# 09_Misc.net
KiCad netlist of a schematic drawn in Altium Designer
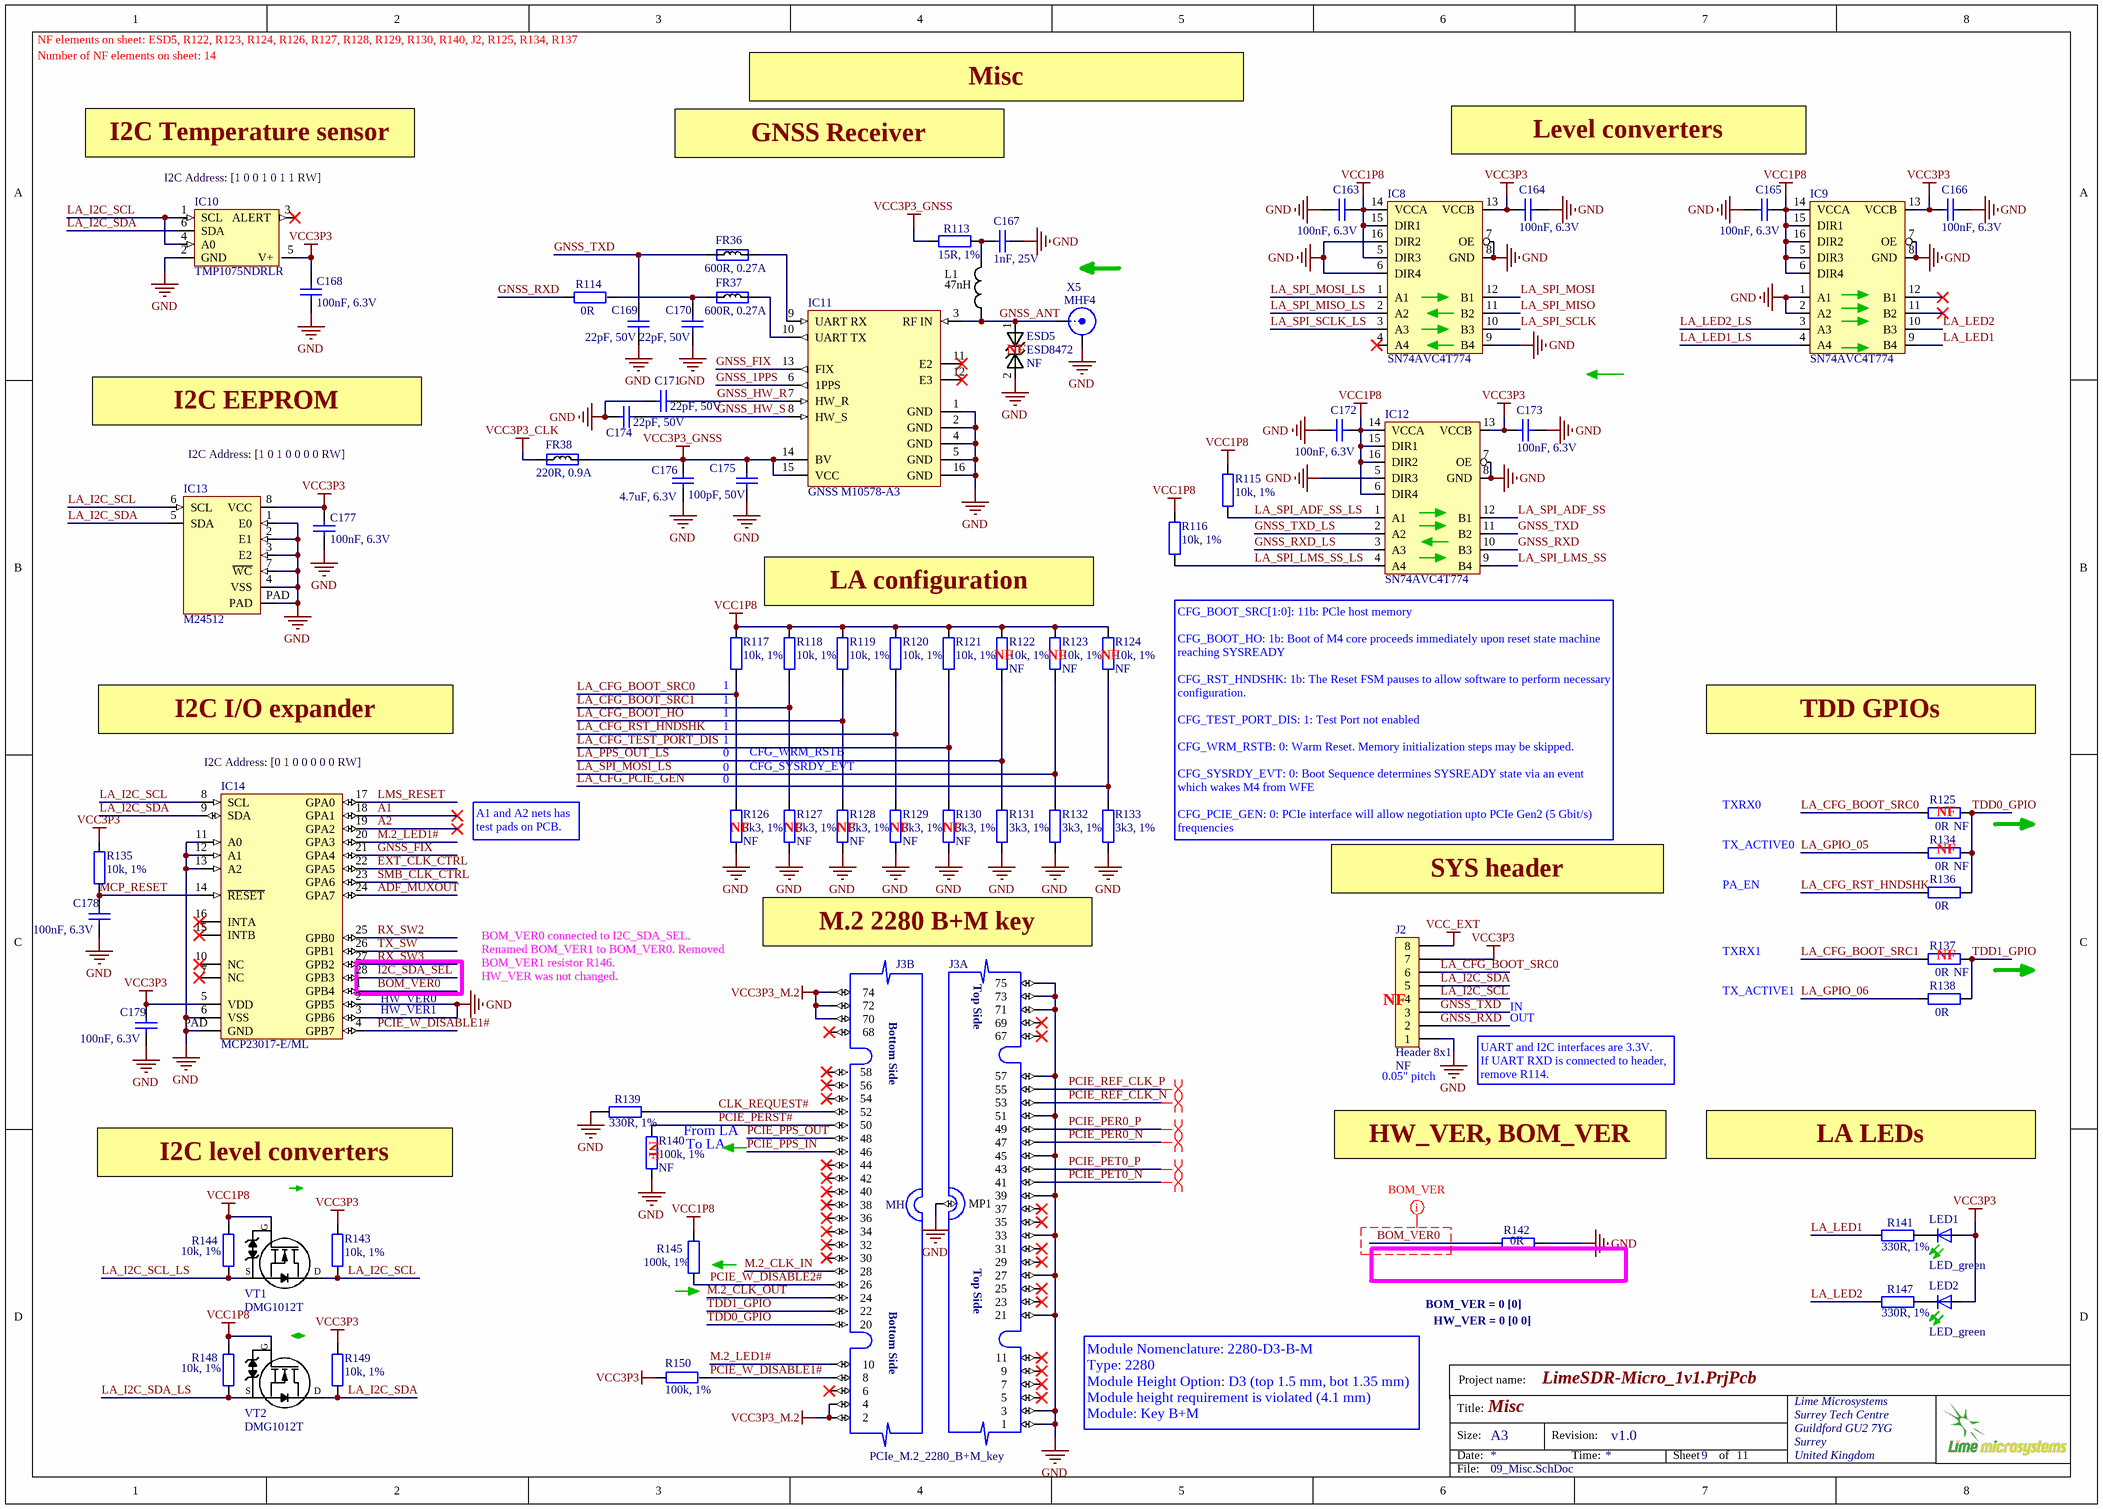
[diagram p0: 09_Misc.SchDoc]

(export (version "E")
  (design (tool "Eeschema 10.0.6"))
  (components
    (comp (ref "C163")
      (value "100nF, 6.3V")
      (footprint "CAP0201")
      (fields (field (name "MANUFACTURER") "Samsung") (field (name "TOLERANCE") "20%"))
      (libsource (lib "LimeMicroAltiumLib_schLib") (part "Cap_0402"))
    )
    (comp (ref "C164")
      (value "100nF, 6.3V")
      (footprint "CAP0201")
      (fields (field (name "MANUFACTURER") "Samsung") (field (name "TOLERANCE") "20%"))
      (libsource (lib "LimeMicroAltiumLib_schLib") (part "Cap_0402"))
    )
    (comp (ref "C165")
      (value "100nF, 6.3V")
      (footprint "CAP0201")
      (fields (field (name "MANUFACTURER") "Samsung") (field (name "TOLERANCE") "20%"))
      (libsource (lib "LimeMicroAltiumLib_schLib") (part "Cap_0402"))
    )
    (comp (ref "C166")
      (value "100nF, 6.3V")
      (footprint "CAP0201")
      (fields (field (name "MANUFACTURER") "Samsung") (field (name "TOLERANCE") "20%"))
      (libsource (lib "LimeMicroAltiumLib_schLib") (part "Cap_0402"))
    )
    (comp (ref "C167")
      (value "1nF, 25V")
      (footprint "CAP0201")
      (fields (field (name "TOLERANCE") "±10%") (field (name "MANUFACTURER") "TDK Corporation"))
      (libsource (lib "LimeMicroAltiumLib_schLib") (part "Cap_0402"))
    )
    (comp (ref "C168")
      (value "100nF, 6.3V")
      (footprint "CAP0201")
      (fields (field (name "MANUFACTURER") "Samsung") (field (name "TOLERANCE") "20%"))
      (libsource (lib "LimeMicroAltiumLib_schLib") (part "Cap_0402"))
    )
    (comp (ref "C169")
      (value "22pF, 50V")
      (footprint "CAP0201")
      (fields
        (field (name "MANUFACTURER") "Murata")
        (field (name "TOLERANCE") "5%")
        (field (name "VOLTAGE") "50V")
      )
      (libsource (lib "LimeMicroAltiumLib_schLib") (part "Cap_0402"))
    )
    (comp (ref "C170")
      (value "22pF, 50V")
      (footprint "CAP0201")
      (fields
        (field (name "MANUFACTURER") "Murata")
        (field (name "TOLERANCE") "5%")
        (field (name "VOLTAGE") "50V")
      )
      (libsource (lib "LimeMicroAltiumLib_schLib") (part "Cap_0402"))
    )
    (comp (ref "C171")
      (value "22pF, 50V")
      (footprint "CAP0201")
      (fields
        (field (name "MANUFACTURER") "Murata")
        (field (name "TOLERANCE") "5%")
        (field (name "VOLTAGE") "50V")
      )
      (libsource (lib "LimeMicroAltiumLib_schLib") (part "Cap_0402"))
    )
    (comp (ref "C172")
      (value "100nF, 6.3V")
      (footprint "CAP0201")
      (fields (field (name "MANUFACTURER") "Samsung") (field (name "TOLERANCE") "20%"))
      (libsource (lib "LimeMicroAltiumLib_schLib") (part "Cap_0402"))
    )
    (comp (ref "C173")
      (value "100nF, 6.3V")
      (footprint "CAP0201")
      (fields (field (name "MANUFACTURER") "Samsung") (field (name "TOLERANCE") "20%"))
      (libsource (lib "LimeMicroAltiumLib_schLib") (part "Cap_0402"))
    )
    (comp (ref "C174")
      (value "22pF, 50V")
      (footprint "CAP0201")
      (fields
        (field (name "MANUFACTURER") "Murata")
        (field (name "TOLERANCE") "5%")
        (field (name "VOLTAGE") "50V")
      )
      (libsource (lib "LimeMicroAltiumLib_schLib") (part "Cap_0402"))
    )
    (comp (ref "C175")
      (value "100pF, 50V")
      (footprint "CAP0201")
      (fields
        (field (name "MANUFACTURER") "TDK")
        (field (name "TOLERANCE") "5%")
        (field (name "VOLTAGE") "50V")
      )
      (libsource (lib "LimeMicroAltiumLib_schLib") (part "Cap_0402"))
    )
    (comp (ref "C176")
      (value "4.7uF, 6.3V")
      (footprint "CAP0402")
      (fields
        (field (name "MANUFACTURER") "Murata Electronics North America")
        (field (name "TOLERANCE") "±20%")
      )
      (libsource (lib "LimeMicroAltiumLib_schLib") (part "Cap_0402"))
    )
    (comp (ref "C177")
      (value "100nF, 6.3V")
      (footprint "CAP0201")
      (fields (field (name "MANUFACTURER") "Samsung") (field (name "TOLERANCE") "20%"))
      (libsource (lib "LimeMicroAltiumLib_schLib") (part "Cap_0402"))
    )
    (comp (ref "C178")
      (value "100nF, 6.3V")
      (footprint "CAP0201")
      (fields (field (name "MANUFACTURER") "Samsung") (field (name "TOLERANCE") "20%"))
      (libsource (lib "LimeMicroAltiumLib_schLib") (part "Cap_0402"))
    )
    (comp (ref "C179")
      (value "100nF, 6.3V")
      (footprint "CAP0201")
      (fields (field (name "MANUFACTURER") "Samsung") (field (name "TOLERANCE") "20%"))
      (libsource (lib "LimeMicroAltiumLib_schLib") (part "Cap_0402"))
    )
    (comp (ref "ESD5")
      (value "ESD8472")
      (footprint "ESD8472_X3DFN2")
      (fields (field (name "MANUFACTURER") "ON Semiconductor") (field (name "ASSEMBLY INFO") "NF"))
      (libsource (lib "LimeMicroAltiumLib_schLib") (part "ESD8472"))
    )
    (comp (ref "FR36")
      (value "600R, 0.27A")
      (footprint "RES0201")
      (fields (field (name "MANUFACTURER") "Taiyo Yuden"))
      (libsource (lib "LimeMicroAltiumLib_schLib") (part "Ferrite"))
    )
    (comp (ref "FR37")
      (value "600R, 0.27A")
      (footprint "RES0201")
      (fields (field (name "MANUFACTURER") "Taiyo Yuden"))
      (libsource (lib "LimeMicroAltiumLib_schLib") (part "Ferrite"))
    )
    (comp (ref "FR38")
      (value "220R, 0.9A")
      (footprint "RES0402")
      (fields (field (name "MANUFACTURER") "TDK Corporation"))
      (libsource (lib "LimeFPGAboard_schLib") (part "Ferrite"))
    )
    (comp (ref "IC8")
      (value "SN74AVC4T774")
      (footprint "SN74AVC4T774_v1")
      (fields (field (name "MANUFACTURER") "Texas Instruments"))
      (libsource (lib "LimeMicroAltiumLib") (part "SN74AVC4T774"))
    )
    (comp (ref "IC9")
      (value "SN74AVC4T774")
      (footprint "SN74AVC4T774_v1")
      (fields (field (name "MANUFACTURER") "Texas Instruments"))
      (libsource (lib "LimeMicroAltiumLib") (part "SN74AVC4T774"))
    )
    (comp (ref "IC10")
      (value "TMP1075NDRLR")
      (footprint "TMP1075NDRLR_temperature_sensor_SOT563")
      (fields (field (name "MANUFACTURER") "Texas Instruments"))
      (libsource (lib "LimeMicroAltiumLib_schLib_r04") (part "TMP1075NDRLR_temperature_sensor"))
    )
    (comp (ref "IC11")
      (value "GNSS M10578-A3")
      (footprint "M10578-A3_v2")
      (fields (field (name "MANUFACTURER") "Antenova"))
      (libsource (lib "LimeMicroAltiumLib_schLib_r04") (part "M10578-A3_GPS_GNSS"))
    )
    (comp (ref "IC12")
      (value "SN74AVC4T774")
      (footprint "SN74AVC4T774_v1")
      (fields (field (name "MANUFACTURER") "Texas Instruments"))
      (libsource (lib "LimeMicroAltiumLib") (part "SN74AVC4T774"))
    )
    (comp (ref "IC13")
      (value "M24512")
      (footprint "M24128-DFMC6TG")
      (fields (field (name "MANUFACTURER") "STMicroelectronics"))
      (libsource (lib "LimeMicroAltiumLib_schLib") (part "M24128-DFMC6TG"))
    )
    (comp (ref "IC14")
      (value "MCP23017-E/ML")
      (footprint "MCP23017-E/ML_QFN28")
      (fields (field (name "MANUFACTURER") "Microchip"))
      (libsource (lib "LimeMicroAltiumLib") (part "MCP23017-E/ML_I2C_expander"))
    )
    (comp (ref "J2")
      (value "Header 8x1")
      (footprint "HEADER_8x1_TH_HALF_PITCH")
      (description "Header, 8-Pin, Single row")
      (fields (field (name "ASSEMBLY INFO") "NF") (field (name "MANUFACTURER") "Harwin"))
      (libsource (lib "LimeMicroAltiumLib") (part "Header 8x1"))
    )
    (comp (ref "J3")
      (value "PCIe_M.2_2280_B+M_key")
      (footprint "PCIe_M.2_2280_B+M_key")
      (libsource (lib "") (part "PCIe_M.2_2280_B+M_key_1"))
    )
    (comp (ref "L1")
      (value "47nH")
      (footprint "RES0402")
      (fields
        (field (name "MANUFACTURER") "COILCRAFT")
        (field (name "MANUFACTURER PART NUMBER") "0402HP-47NXJLU")
      )
      (libsource (lib "LimeMicroAltiumLib_schLib") (part "Inductor_0603"))
    )
    (comp (ref "LED1")
      (value "LED_green")
      (footprint "LED0201")
      (fields (field (name "MANUFACTURER") "Kingbright"))
      (libsource (lib "LimeFPGAboard_schLib") (part "LED_green"))
    )
    (comp (ref "LED2")
      (value "LED_green")
      (footprint "LED0201")
      (fields (field (name "MANUFACTURER") "Kingbright"))
      (libsource (lib "LimeFPGAboard_schLib") (part "LED_green"))
    )
    (comp (ref "R113")
      (value "15R, 1%")
      (footprint "RES0201")
      (fields (field (name "MANUFACTURER") "Yageo") (field (name "TOLERANCE") "1%"))
      (libsource (lib "LimeFPGAboard_schLib") (part "Res_0402"))
    )
    (comp (ref "R114")
      (value "0R")
      (footprint "RES0201")
      (fields (field (name "MANUFACTURER") "Yageo") (field (name "TOLERANCE") "5%"))
      (libsource (lib "LimeFPGAboard_schLib") (part "Res_0402"))
    )
    (comp (ref "R115")
      (value "10k, 1%")
      (footprint "RES0201")
      (fields (field (name "MANUFACTURER") "Yageo") (field (name "TOLERANCE") "1%"))
      (libsource (lib "LimeFPGAboard_schLib") (part "Res_0402"))
    )
    (comp (ref "R116")
      (value "10k, 1%")
      (footprint "RES0201")
      (fields (field (name "MANUFACTURER") "Yageo") (field (name "TOLERANCE") "1%"))
      (libsource (lib "LimeFPGAboard_schLib") (part "Res_0402"))
    )
    (comp (ref "R117")
      (value "10k, 1%")
      (footprint "RES0201")
      (fields (field (name "MANUFACTURER") "Yageo") (field (name "TOLERANCE") "1%"))
      (libsource (lib "LimeFPGAboard_schLib") (part "Res_0402"))
    )
    (comp (ref "R118")
      (value "10k, 1%")
      (footprint "RES0201")
      (fields (field (name "MANUFACTURER") "Yageo") (field (name "TOLERANCE") "1%"))
      (libsource (lib "LimeFPGAboard_schLib") (part "Res_0402"))
    )
    (comp (ref "R119")
      (value "10k, 1%")
      (footprint "RES0201")
      (fields (field (name "MANUFACTURER") "Yageo") (field (name "TOLERANCE") "1%"))
      (libsource (lib "LimeFPGAboard_schLib") (part "Res_0402"))
    )
    (comp (ref "R120")
      (value "10k, 1%")
      (footprint "RES0201")
      (fields (field (name "MANUFACTURER") "Yageo") (field (name "TOLERANCE") "1%"))
      (libsource (lib "LimeFPGAboard_schLib") (part "Res_0402"))
    )
    (comp (ref "R121")
      (value "10k, 1%")
      (footprint "RES0201")
      (fields (field (name "MANUFACTURER") "Yageo") (field (name "TOLERANCE") "1%"))
      (libsource (lib "LimeFPGAboard_schLib") (part "Res_0402"))
    )
    (comp (ref "R122")
      (value "10k, 1%")
      (footprint "RES0201")
      (fields
        (field (name "ASSEMBLY INFO") "NF")
        (field (name "MANUFACTURER") "Yageo")
        (field (name "TOLERANCE") "1%")
      )
      (libsource (lib "LimeFPGAboard_schLib") (part "Res_0402"))
    )
    (comp (ref "R123")
      (value "10k, 1%")
      (footprint "RES0201")
      (fields
        (field (name "ASSEMBLY INFO") "NF")
        (field (name "MANUFACTURER") "Yageo")
        (field (name "TOLERANCE") "1%")
      )
      (libsource (lib "LimeFPGAboard_schLib") (part "Res_0402"))
    )
    (comp (ref "R124")
      (value "10k, 1%")
      (footprint "RES0201")
      (fields
        (field (name "ASSEMBLY INFO") "NF")
        (field (name "MANUFACTURER") "Yageo")
        (field (name "TOLERANCE") "1%")
      )
      (libsource (lib "LimeFPGAboard_schLib") (part "Res_0402"))
    )
    (comp (ref "R125")
      (value "0R")
      (footprint "RES0201")
      (fields
        (field (name "ASSEMBLY INFO") "NF")
        (field (name "MANUFACTURER") "Yageo")
        (field (name "TOLERANCE") "5%")
      )
      (libsource (lib "LimeFPGAboard_schLib") (part "Res_0402"))
    )
    (comp (ref "R126")
      (value "3k3, 1%")
      (footprint "RES0201")
      (fields
        (field (name "ASSEMBLY INFO") "NF")
        (field (name "MANUFACTURER") "Yageo")
        (field (name "TOLERANCE") "1%")
      )
      (libsource (lib "LimeFPGAboard_schLib") (part "Res_0402"))
    )
    (comp (ref "R127")
      (value "3k3, 1%")
      (footprint "RES0201")
      (fields
        (field (name "ASSEMBLY INFO") "NF")
        (field (name "MANUFACTURER") "Yageo")
        (field (name "TOLERANCE") "1%")
      )
      (libsource (lib "LimeFPGAboard_schLib") (part "Res_0402"))
    )
    (comp (ref "R128")
      (value "3k3, 1%")
      (footprint "RES0201")
      (fields
        (field (name "ASSEMBLY INFO") "NF")
        (field (name "MANUFACTURER") "Yageo")
        (field (name "TOLERANCE") "1%")
      )
      (libsource (lib "LimeFPGAboard_schLib") (part "Res_0402"))
    )
    (comp (ref "R129")
      (value "3k3, 1%")
      (footprint "RES0201")
      (fields
        (field (name "ASSEMBLY INFO") "NF")
        (field (name "MANUFACTURER") "Yageo")
        (field (name "TOLERANCE") "1%")
      )
      (libsource (lib "LimeFPGAboard_schLib") (part "Res_0402"))
    )
    (comp (ref "R130")
      (value "3k3, 1%")
      (footprint "RES0201")
      (fields
        (field (name "ASSEMBLY INFO") "NF")
        (field (name "MANUFACTURER") "Yageo")
        (field (name "TOLERANCE") "1%")
      )
      (libsource (lib "LimeFPGAboard_schLib") (part "Res_0402"))
    )
    (comp (ref "R131")
      (value "3k3, 1%")
      (footprint "RES0201")
      (fields (field (name "MANUFACTURER") "Yageo") (field (name "TOLERANCE") "1%"))
      (libsource (lib "LimeFPGAboard_schLib") (part "Res_0402"))
    )
    (comp (ref "R132")
      (value "3k3, 1%")
      (footprint "RES0201")
      (fields (field (name "MANUFACTURER") "Yageo") (field (name "TOLERANCE") "1%"))
      (libsource (lib "LimeFPGAboard_schLib") (part "Res_0402"))
    )
    (comp (ref "R133")
      (value "3k3, 1%")
      (footprint "RES0201")
      (fields (field (name "MANUFACTURER") "Yageo") (field (name "TOLERANCE") "1%"))
      (libsource (lib "LimeFPGAboard_schLib") (part "Res_0402"))
    )
    (comp (ref "R134")
      (value "0R")
      (footprint "RES0201")
      (fields
        (field (name "ASSEMBLY INFO") "NF")
        (field (name "MANUFACTURER") "Yageo")
        (field (name "TOLERANCE") "5%")
      )
      (libsource (lib "LimeFPGAboard_schLib") (part "Res_0402"))
    )
    (comp (ref "R135")
      (value "10k, 1%")
      (footprint "RES0201")
      (fields (field (name "MANUFACTURER") "Yageo") (field (name "TOLERANCE") "1%"))
      (libsource (lib "LimeFPGAboard_schLib") (part "Res_0402"))
    )
    (comp (ref "R136")
      (value "0R")
      (footprint "RES0201")
      (fields (field (name "MANUFACTURER") "Yageo") (field (name "TOLERANCE") "5%"))
      (libsource (lib "LimeFPGAboard_schLib") (part "Res_0402"))
    )
    (comp (ref "R137")
      (value "0R")
      (footprint "RES0201")
      (fields
        (field (name "ASSEMBLY INFO") "NF")
        (field (name "MANUFACTURER") "Yageo")
        (field (name "TOLERANCE") "5%")
      )
      (libsource (lib "LimeFPGAboard_schLib") (part "Res_0402"))
    )
    (comp (ref "R138")
      (value "0R")
      (footprint "RES0201")
      (fields (field (name "MANUFACTURER") "Yageo") (field (name "TOLERANCE") "5%"))
      (libsource (lib "LimeFPGAboard_schLib") (part "Res_0402"))
    )
    (comp (ref "R139")
      (value "330R, 1%")
      (footprint "RES0201")
      (fields (field (name "MANUFACTURER") "Vishay Dale") (field (name "TOLERANCE") "1%"))
      (libsource (lib "LimeFPGAboard_schLib") (part "Res_0402"))
    )
    (comp (ref "R140")
      (value "100k, 1%")
      (footprint "RES0201")
      (fields
        (field (name "ASSEMBLY INFO") "NF")
        (field (name "MANUFACTURER") "Yageo")
        (field (name "TOLERANCE") "1%")
      )
      (libsource (lib "LimeMicroAltiumLib_schLib") (part "Res_0402"))
    )
    (comp (ref "R141")
      (value "330R, 1%")
      (footprint "RES0201")
      (fields (field (name "MANUFACTURER") "Vishay Dale") (field (name "TOLERANCE") "1%"))
      (libsource (lib "LimeFPGAboard_schLib") (part "Res_0402"))
    )
    (comp (ref "R142")
      (value "0R")
      (footprint "RES0201")
      (fields (field (name "MANUFACTURER") "Yageo") (field (name "TOLERANCE") "5%"))
      (libsource (lib "LimeFPGAboard_schLib") (part "Res_0402"))
    )
    (comp (ref "R143")
      (value "10k, 1%")
      (footprint "RES0201")
      (fields (field (name "MANUFACTURER") "Yageo") (field (name "TOLERANCE") "1%"))
      (libsource (lib "LimeFPGAboard_schLib") (part "Res_0402"))
    )
    (comp (ref "R144")
      (value "10k, 1%")
      (footprint "RES0201")
      (fields (field (name "MANUFACTURER") "Yageo") (field (name "TOLERANCE") "1%"))
      (libsource (lib "LimeFPGAboard_schLib") (part "Res_0402"))
    )
    (comp (ref "R145")
      (value "100k, 1%")
      (footprint "RES0201")
      (fields (field (name "MANUFACTURER") "Yageo") (field (name "TOLERANCE") "1%"))
      (libsource (lib "LimeMicroAltiumLib_schLib") (part "Res_0402"))
    )
    (comp (ref "R147")
      (value "330R, 1%")
      (footprint "RES0201")
      (fields (field (name "MANUFACTURER") "Vishay Dale") (field (name "TOLERANCE") "1%"))
      (libsource (lib "LimeFPGAboard_schLib") (part "Res_0402"))
    )
    (comp (ref "R148")
      (value "10k, 1%")
      (footprint "RES0201")
      (fields (field (name "MANUFACTURER") "Yageo") (field (name "TOLERANCE") "1%"))
      (libsource (lib "LimeFPGAboard_schLib") (part "Res_0402"))
    )
    (comp (ref "R149")
      (value "10k, 1%")
      (footprint "RES0201")
      (fields (field (name "MANUFACTURER") "Yageo") (field (name "TOLERANCE") "1%"))
      (libsource (lib "LimeFPGAboard_schLib") (part "Res_0402"))
    )
    (comp (ref "R150")
      (value "100k, 1%")
      (footprint "RES0201")
      (fields (field (name "MANUFACTURER") "Yageo") (field (name "TOLERANCE") "1%"))
      (libsource (lib "LimeMicroAltiumLib_schLib") (part "Res_0402"))
    )
    (comp (ref "VT1")
      (value "DMG1012T")
      (footprint "SOT523")
      (fields (field (name "MANUFACTURER") "Diodes Incorporated"))
      (libsource (lib "LimeMicroAltiumLib_schLib_r01") (part "DMG1012T"))
    )
    (comp (ref "VT2")
      (value "DMG1012T")
      (footprint "SOT523")
      (fields (field (name "MANUFACTURER") "Diodes Incorporated"))
      (libsource (lib "LimeMicroAltiumLib_schLib_r01") (part "DMG1012T"))
    )
    (comp (ref "X5")
      (value "MHF4")
      (footprint "IPEX_MHF4_conn")
      (description "IPEX MHF4 Connector Jack, Male Pin 50 Ohms Surface Mount Solder")
      (fields (field (name "MANUFACTURER") "TE Connectivity / Linx Technologies"))
      (libsource (lib "LimeMicroAltiumLib_schLib") (part "RF_IF_connector"))
    )
  )
  (nets
    (net (code "1") (name "/A1") (class "Default")
      (node (ref "IC14") (pin "18") (pinfunction "GPA1_18") (pintype "bidirectional+no_connect"))
    )
    (net (code "2") (name "/A2") (class "Default")
      (node (ref "IC14") (pin "19") (pinfunction "GPA2_19") (pintype "bidirectional+no_connect"))
    )
    (net (code "3") (name "/ADF_MUXOUT") (class "Default")
      (node (ref "IC14") (pin "24") (pinfunction "GPA7_24") (pintype "bidirectional"))
    )
    (net (code "4") (name "/BOM_VER0") (class "Default")
      (node (ref "IC14") (pin "1") (pinfunction "GPB4_1") (pintype "bidirectional"))
      (node (ref "R142") (pin "1") (pinfunction "1_1") (pintype "passive"))
    )
    (net (code "5") (name "/CLK_REQUEST#") (class "Default")
      (node (ref "J3") (pin "P52") (pinfunction "52_P52") (pintype "bidirectional"))
      (node (ref "R139") (pin "1") (pinfunction "1_1") (pintype "passive"))
    )
    (net (code "6") (name "/EXT_CLK_CTRL") (class "Default")
      (node (ref "IC14") (pin "22") (pinfunction "GPA5_22") (pintype "bidirectional"))
    )
    (net (code "7") (name "/GNSS_1PPS") (class "Default")
      (node (ref "IC11") (pin "6") (pinfunction "1PPS_6") (pintype "output"))
    )
    (net (code "8") (name "/GNSS_ANT") (class "Default")
      (node (ref "ESD5") (pin "1") (pinfunction "1_1") (pintype "passive"))
      (node (ref "IC11") (pin "3") (pinfunction "RF_IN_3") (pintype "input"))
      (node (ref "L1") (pin "1") (pinfunction "1_1") (pintype "passive"))
      (node (ref "X5") (pin "1") (pinfunction "X_1") (pintype "passive"))
    )
    (net (code "9") (name "/GNSS_FIX") (class "Default")
      (node (ref "IC11") (pin "13") (pinfunction "FIX_13") (pintype "output"))
      (node (ref "IC14") (pin "21") (pinfunction "GPA4_21") (pintype "bidirectional"))
    )
    (net (code "10") (name "/GNSS_HW_R") (class "Default")
      (node (ref "C171") (pin "1") (pinfunction "1_1") (pintype "passive"))
      (node (ref "IC11") (pin "7") (pinfunction "HW_R_7") (pintype "input"))
    )
    (net (code "11") (name "/GNSS_HW_S") (class "Default")
      (node (ref "C174") (pin "1") (pinfunction "1_1") (pintype "passive"))
      (node (ref "IC11") (pin "8") (pinfunction "HW_S_8") (pintype "input"))
    )
    (net (code "12") (name "/GNSS_RXD") (class "Default")
      (node (ref "IC12") (pin "10") (pinfunction "B3_10") (pintype "passive"))
      (node (ref "J2") (pin "2") (pinfunction "2_2") (pintype "passive"))
      (node (ref "R114") (pin "1") (pinfunction "1_1") (pintype "passive"))
    )
    (net (code "13") (name "/GNSS_RXD_LS") (class "Default")
      (node (ref "IC12") (pin "3") (pinfunction "A3_3") (pintype "passive"))
    )
    (net (code "14") (name "/GNSS_TXD") (class "Default")
      (node (ref "C169") (pin "1") (pinfunction "1_1") (pintype "passive"))
      (node (ref "FR36") (pin "1") (pinfunction "1_1") (pintype "passive"))
      (node (ref "IC12") (pin "11") (pinfunction "B2_11") (pintype "passive"))
      (node (ref "J2") (pin "3") (pinfunction "3_3") (pintype "passive"))
    )
    (net (code "15") (name "/GNSS_TXD_LS") (class "Default")
      (node (ref "IC12") (pin "2") (pinfunction "A2_2") (pintype "passive"))
    )
    (net (code "16") (name "/I2C_SDA_SEL") (class "Default")
      (node (ref "IC14") (pin "28") (pinfunction "GPB3_28") (pintype "bidirectional"))
    )
    (net (code "17") (name "/LA_CFG_BOOT_HO") (class "Default")
      (node (ref "R119") (pin "2") (pinfunction "2_2") (pintype "passive"))
      (node (ref "R128") (pin "1") (pinfunction "1_1") (pintype "passive"))
    )
    (net (code "18") (name "/LA_CFG_BOOT_SRC0") (class "Default")
      (node (ref "J2") (pin "6") (pinfunction "6_6") (pintype "passive"))
      (node (ref "R117") (pin "2") (pinfunction "2_2") (pintype "passive"))
      (node (ref "R125") (pin "1") (pinfunction "1_1") (pintype "passive"))
      (node (ref "R126") (pin "1") (pinfunction "1_1") (pintype "passive"))
    )
    (net (code "19") (name "/LA_CFG_BOOT_SRC1") (class "Default")
      (node (ref "R118") (pin "2") (pinfunction "2_2") (pintype "passive"))
      (node (ref "R127") (pin "1") (pinfunction "1_1") (pintype "passive"))
      (node (ref "R137") (pin "1") (pinfunction "1_1") (pintype "passive"))
    )
    (net (code "20") (name "/LA_CFG_PCIE_GEN") (class "Default")
      (node (ref "R124") (pin "2") (pinfunction "2_2") (pintype "passive"))
      (node (ref "R133") (pin "1") (pinfunction "1_1") (pintype "passive"))
    )
    (net (code "21") (name "/LA_CFG_RST_HNDSHK") (class "Default")
      (node (ref "R120") (pin "2") (pinfunction "2_2") (pintype "passive"))
      (node (ref "R129") (pin "1") (pinfunction "1_1") (pintype "passive"))
      (node (ref "R136") (pin "1") (pinfunction "1_1") (pintype "passive"))
    )
    (net (code "22") (name "/LA_CFG_TEST_PORT_DIS") (class "Default")
      (node (ref "R121") (pin "2") (pinfunction "2_2") (pintype "passive"))
      (node (ref "R130") (pin "1") (pinfunction "1_1") (pintype "passive"))
    )
    (net (code "23") (name "/LA_GPIO_05") (class "Default")
      (node (ref "R134") (pin "1") (pinfunction "1_1") (pintype "passive"))
    )
    (net (code "24") (name "/LA_GPIO_06") (class "Default")
      (node (ref "R138") (pin "1") (pinfunction "1_1") (pintype "passive"))
    )
    (net (code "25") (name "/LA_I2C_SCL") (class "Default")
      (node (ref "IC10") (pin "1") (pinfunction "SCL_1") (pintype "input"))
      (node (ref "IC10") (pin "4") (pinfunction "A0_4") (pintype "input"))
      (node (ref "IC13") (pin "6") (pinfunction "SCL_6") (pintype "input"))
      (node (ref "IC14") (pin "8") (pinfunction "SCL_8") (pintype "input"))
      (node (ref "J2") (pin "4") (pinfunction "4_4") (pintype "passive"))
      (node (ref "R143") (pin "2") (pinfunction "2_2") (pintype "passive"))
      (node (ref "VT1") (pin "D") (pinfunction "D_D") (pintype "passive"))
    )
    (net (code "26") (name "/LA_I2C_SCL_LS") (class "Default")
      (node (ref "R144") (pin "2") (pinfunction "2_2") (pintype "passive"))
      (node (ref "VT1") (pin "S") (pinfunction "S_S") (pintype "passive"))
    )
    (net (code "27") (name "/LA_I2C_SDA") (class "Default")
      (node (ref "IC10") (pin "6") (pinfunction "SDA_6") (pintype "bidirectional"))
      (node (ref "IC13") (pin "5") (pinfunction "SDA_5") (pintype "bidirectional"))
      (node (ref "IC14") (pin "9") (pinfunction "SDA_9") (pintype "bidirectional"))
      (node (ref "J2") (pin "5") (pinfunction "5_5") (pintype "passive"))
      (node (ref "R149") (pin "2") (pinfunction "2_2") (pintype "passive"))
      (node (ref "VT2") (pin "D") (pinfunction "D_D") (pintype "passive"))
    )
    (net (code "28") (name "/LA_I2C_SDA_LS") (class "Default")
      (node (ref "R148") (pin "2") (pinfunction "2_2") (pintype "passive"))
      (node (ref "VT2") (pin "S") (pinfunction "S_S") (pintype "passive"))
    )
    (net (code "29") (name "/LA_LED1") (class "Default")
      (node (ref "IC9") (pin "9") (pinfunction "B4_9") (pintype "passive"))
      (node (ref "R141") (pin "2") (pinfunction "2_2") (pintype "passive"))
    )
    (net (code "30") (name "/LA_LED1_LS") (class "Default")
      (node (ref "IC9") (pin "4") (pinfunction "A4_4") (pintype "passive"))
    )
    (net (code "31") (name "/LA_LED2") (class "Default")
      (node (ref "IC9") (pin "10") (pinfunction "B3_10") (pintype "passive"))
      (node (ref "R147") (pin "2") (pinfunction "2_2") (pintype "passive"))
    )
    (net (code "32") (name "/LA_LED2_LS") (class "Default")
      (node (ref "IC9") (pin "3") (pinfunction "A3_3") (pintype "passive"))
    )
    (net (code "33") (name "/LA_PPS_OUT_LS") (class "Default")
      (node (ref "R122") (pin "2") (pinfunction "2_2") (pintype "passive"))
      (node (ref "R131") (pin "1") (pinfunction "1_1") (pintype "passive"))
    )
    (net (code "34") (name "/LA_SPI_ADF_SS") (class "Default")
      (node (ref "IC12") (pin "12") (pinfunction "B1_12") (pintype "passive"))
    )
    (net (code "35") (name "/LA_SPI_ADF_SS_LS") (class "Default")
      (node (ref "IC12") (pin "1") (pinfunction "A1_1") (pintype "passive"))
      (node (ref "R115") (pin "2") (pinfunction "2_2") (pintype "passive"))
    )
    (net (code "36") (name "/LA_SPI_LMS_SS") (class "Default")
      (node (ref "IC12") (pin "9") (pinfunction "B4_9") (pintype "passive"))
    )
    (net (code "37") (name "/LA_SPI_LMS_SS_LS") (class "Default")
      (node (ref "IC12") (pin "4") (pinfunction "A4_4") (pintype "passive"))
      (node (ref "R116") (pin "2") (pinfunction "2_2") (pintype "passive"))
    )
    (net (code "38") (name "/LA_SPI_MISO") (class "Default")
      (node (ref "IC8") (pin "11") (pinfunction "B2_11") (pintype "passive"))
    )
    (net (code "39") (name "/LA_SPI_MISO_LS") (class "Default")
      (node (ref "IC8") (pin "2") (pinfunction "A2_2") (pintype "passive"))
    )
    (net (code "40") (name "/LA_SPI_MOSI") (class "Default")
      (node (ref "IC8") (pin "12") (pinfunction "B1_12") (pintype "passive"))
    )
    (net (code "41") (name "/LA_SPI_MOSI_LS") (class "Default")
      (node (ref "IC8") (pin "1") (pinfunction "A1_1") (pintype "passive"))
      (node (ref "R123") (pin "2") (pinfunction "2_2") (pintype "passive"))
      (node (ref "R132") (pin "1") (pinfunction "1_1") (pintype "passive"))
    )
    (net (code "42") (name "/LA_SPI_SCLK") (class "Default")
      (node (ref "IC8") (pin "10") (pinfunction "B3_10") (pintype "passive"))
    )
    (net (code "43") (name "/LA_SPI_SCLK_LS") (class "Default")
      (node (ref "IC8") (pin "3") (pinfunction "A3_3") (pintype "passive"))
    )
    (net (code "44") (name "/LMS_RESET") (class "Default")
      (node (ref "IC14") (pin "17") (pinfunction "GPA0_17") (pintype "bidirectional"))
    )
    (net (code "45") (name "/M.2_CLK_IN") (class "Default")
      (node (ref "J3") (pin "P28") (pinfunction "28_P28") (pintype "bidirectional"))
    )
    (net (code "46") (name "/M.2_CLK_OUT") (class "Default")
      (node (ref "J3") (pin "P24") (pinfunction "24_P24") (pintype "bidirectional"))
    )
    (net (code "47") (name "/M.2_LED1#") (class "Default")
      (node (ref "IC14") (pin "20") (pinfunction "GPA3_20") (pintype "bidirectional"))
      (node (ref "J3") (pin "P10") (pinfunction "10_P10") (pintype "bidirectional"))
    )
    (net (code "48") (name "/MCP_RESET") (class "Default")
      (node (ref "C178") (pin "1") (pinfunction "1_1") (pintype "passive"))
      (node (ref "IC14") (pin "14") (pinfunction "~{RESET}_14") (pintype "input"))
      (node (ref "R135") (pin "2") (pinfunction "2_2") (pintype "passive"))
    )
    (net (code "49") (name "/PCIE_PER0_N") (class "Default")
      (node (ref "J3") (pin "P47") (pinfunction "47_P47") (pintype "bidirectional"))
    )
    (net (code "50") (name "/PCIE_PER0_P") (class "Default")
      (node (ref "J3") (pin "P49") (pinfunction "49_P49") (pintype "bidirectional"))
    )
    (net (code "51") (name "/PCIE_PERST#") (class "Default")
      (node (ref "J3") (pin "P50") (pinfunction "50_P50") (pintype "bidirectional"))
      (node (ref "R140") (pin "2") (pinfunction "2_2") (pintype "passive"))
    )
    (net (code "52") (name "/PCIE_PET0_N") (class "Default")
      (node (ref "J3") (pin "P41") (pinfunction "41_P41") (pintype "bidirectional"))
    )
    (net (code "53") (name "/PCIE_PET0_P") (class "Default")
      (node (ref "J3") (pin "P43") (pinfunction "43_P43") (pintype "bidirectional"))
    )
    (net (code "54") (name "/PCIE_PPS_IN") (class "Default")
      (node (ref "J3") (pin "P46") (pinfunction "46_P46") (pintype "bidirectional"))
    )
    (net (code "55") (name "/PCIE_PPS_OUT") (class "Default")
      (node (ref "J3") (pin "P48") (pinfunction "48_P48") (pintype "bidirectional"))
    )
    (net (code "56") (name "/PCIE_REF_CLK_N") (class "Default")
      (node (ref "J3") (pin "P53") (pinfunction "53_P53") (pintype "bidirectional"))
    )
    (net (code "57") (name "/PCIE_REF_CLK_P") (class "Default")
      (node (ref "J3") (pin "P55") (pinfunction "55_P55") (pintype "bidirectional"))
    )
    (net (code "58") (name "/PCIE_W_DISABLE1#") (class "Default")
      (node (ref "IC14") (pin "4") (pinfunction "GPB7_4") (pintype "bidirectional"))
      (node (ref "J3") (pin "P8") (pinfunction "8_P8") (pintype "bidirectional"))
      (node (ref "R150") (pin "2") (pinfunction "2_2") (pintype "passive"))
    )
    (net (code "59") (name "/PCIE_W_DISABLE2#") (class "Default")
      (node (ref "J3") (pin "P26") (pinfunction "26_P26") (pintype "bidirectional"))
      (node (ref "R145") (pin "2") (pinfunction "2_2") (pintype "passive"))
    )
    (net (code "60") (name "/RX_SW2") (class "Default")
      (node (ref "IC14") (pin "25") (pinfunction "GPB0_25") (pintype "bidirectional"))
    )
    (net (code "61") (name "/RX_SW3") (class "Default")
      (node (ref "IC14") (pin "27") (pinfunction "GPB2_27") (pintype "bidirectional"))
    )
    (net (code "62") (name "/SMB_CLK_CTRL") (class "Default")
      (node (ref "IC14") (pin "23") (pinfunction "GPA6_23") (pintype "bidirectional"))
    )
    (net (code "63") (name "/TDD0_GPIO") (class "Default")
      (node (ref "J3") (pin "P20") (pinfunction "20_P20") (pintype "bidirectional"))
      (node (ref "R125") (pin "2") (pinfunction "2_2") (pintype "passive"))
      (node (ref "R134") (pin "2") (pinfunction "2_2") (pintype "passive"))
      (node (ref "R136") (pin "2") (pinfunction "2_2") (pintype "passive"))
    )
    (net (code "64") (name "/TDD1_GPIO") (class "Default")
      (node (ref "J3") (pin "P22") (pinfunction "22_P22") (pintype "bidirectional"))
      (node (ref "R137") (pin "2") (pinfunction "2_2") (pintype "passive"))
      (node (ref "R138") (pin "2") (pinfunction "2_2") (pintype "passive"))
    )
    (net (code "65") (name "/TX_SW") (class "Default")
      (node (ref "IC14") (pin "26") (pinfunction "GPB1_26") (pintype "bidirectional"))
    )
    (net (code "66") (name "GND") (class "Default")
      (node (ref "C163") (pin "1") (pinfunction "1_1") (pintype "passive"))
      (node (ref "C164") (pin "2") (pinfunction "2_2") (pintype "passive"))
      (node (ref "C165") (pin "1") (pinfunction "1_1") (pintype "passive"))
      (node (ref "C166") (pin "2") (pinfunction "2_2") (pintype "passive"))
      (node (ref "C167") (pin "2") (pinfunction "2_2") (pintype "passive"))
      (node (ref "C168") (pin "2") (pinfunction "2_2") (pintype "passive"))
      (node (ref "C169") (pin "2") (pinfunction "2_2") (pintype "passive"))
      (node (ref "C170") (pin "2") (pinfunction "2_2") (pintype "passive"))
      (node (ref "C171") (pin "2") (pinfunction "2_2") (pintype "passive"))
      (node (ref "C172") (pin "1") (pinfunction "1_1") (pintype "passive"))
      (node (ref "C173") (pin "2") (pinfunction "2_2") (pintype "passive"))
      (node (ref "C174") (pin "2") (pinfunction "2_2") (pintype "passive"))
      (node (ref "C175") (pin "1") (pinfunction "1_1") (pintype "passive"))
      (node (ref "C176") (pin "1") (pinfunction "1_1") (pintype "passive"))
      (node (ref "C177") (pin "2") (pinfunction "2_2") (pintype "passive"))
      (node (ref "C178") (pin "2") (pinfunction "2_2") (pintype "passive"))
      (node (ref "C179") (pin "2") (pinfunction "2_2") (pintype "passive"))
      (node (ref "ESD5") (pin "2") (pinfunction "2_2") (pintype "passive"))
      (node (ref "IC10") (pin "2") (pinfunction "GND_2") (pintype "passive"))
      (node (ref "IC11") (pin "1") (pinfunction "GND_1") (pintype "passive"))
      (node (ref "IC11") (pin "16") (pinfunction "GND_16") (pintype "passive"))
      (node (ref "IC11") (pin "2") (pinfunction "GND_2") (pintype "passive"))
      (node (ref "IC11") (pin "4") (pinfunction "GND_4") (pintype "passive"))
      (node (ref "IC11") (pin "5") (pinfunction "GND_5") (pintype "passive"))
      (node (ref "IC12") (pin "5") (pinfunction "DIR3_5") (pintype "passive"))
      (node (ref "IC12") (pin "7") (pinfunction "OE_7") (pintype "passive"))
      (node (ref "IC12") (pin "8") (pinfunction "GND_8") (pintype "passive"))
      (node (ref "IC13") (pin "1") (pinfunction "E0_1") (pintype "input"))
      (node (ref "IC13") (pin "2") (pinfunction "E1_2") (pintype "input"))
      (node (ref "IC13") (pin "3") (pinfunction "E2_3") (pintype "input"))
      (node (ref "IC13") (pin "4") (pinfunction "VSS_4") (pintype "power_in"))
      (node (ref "IC13") (pin "7") (pinfunction "~{WC}_7") (pintype "input"))
      (node (ref "IC13") (pin "PAD") (pinfunction "PAD_PAD") (pintype "power_in"))
      (node (ref "IC14") (pin "11") (pinfunction "A0_11") (pintype "input"))
      (node (ref "IC14") (pin "12") (pinfunction "A1_12") (pintype "input"))
      (node (ref "IC14") (pin "13") (pinfunction "A2_13") (pintype "input"))
      (node (ref "IC14") (pin "2") (pinfunction "GPB5_2") (pintype "bidirectional"))
      (node (ref "IC14") (pin "3") (pinfunction "GPB6_3") (pintype "bidirectional"))
      (node (ref "IC14") (pin "6") (pinfunction "VSS_6") (pintype "power_in"))
      (node (ref "IC14") (pin "PAD") (pinfunction "GND_PAD") (pintype "passive"))
      (node (ref "IC8") (pin "16") (pinfunction "DIR2_16") (pintype "passive"))
      (node (ref "IC8") (pin "6") (pinfunction "DIR4_6") (pintype "passive"))
      (node (ref "IC8") (pin "7") (pinfunction "OE_7") (pintype "passive"))
      (node (ref "IC8") (pin "8") (pinfunction "GND_8") (pintype "passive"))
      (node (ref "IC8") (pin "9") (pinfunction "B4_9") (pintype "passive"))
      (node (ref "IC9") (pin "1") (pinfunction "A1_1") (pintype "passive"))
      (node (ref "IC9") (pin "2") (pinfunction "A2_2") (pintype "passive"))
      (node (ref "IC9") (pin "7") (pinfunction "OE_7") (pintype "passive"))
      (node (ref "IC9") (pin "8") (pinfunction "GND_8") (pintype "passive"))
      (node (ref "J2") (pin "1") (pinfunction "1_1") (pintype "passive"))
      (node (ref "J3") (pin "MOUNTING-HOLE") (pinfunction "MP1_MOUNTING-HOLE") (pintype "bidirectional"))
      (node (ref "J3") (pin "P1") (pinfunction "1_P1") (pintype "bidirectional"))
      (node (ref "J3") (pin "P21") (pinfunction "21_P21") (pintype "bidirectional"))
      (node (ref "J3") (pin "P27") (pinfunction "27_P27") (pintype "bidirectional"))
      (node (ref "J3") (pin "P3") (pinfunction "3_P3") (pintype "bidirectional"))
      (node (ref "J3") (pin "P33") (pinfunction "33_P33") (pintype "bidirectional"))
      (node (ref "J3") (pin "P39") (pinfunction "39_P39") (pintype "bidirectional"))
      (node (ref "J3") (pin "P45") (pinfunction "45_P45") (pintype "bidirectional"))
      (node (ref "J3") (pin "P51") (pinfunction "51_P51") (pintype "bidirectional"))
      (node (ref "J3") (pin "P57") (pinfunction "57_P57") (pintype "bidirectional"))
      (node (ref "J3") (pin "P71") (pinfunction "71_P71") (pintype "bidirectional"))
      (node (ref "J3") (pin "P73") (pinfunction "73_P73") (pintype "bidirectional"))
      (node (ref "J3") (pin "P75") (pinfunction "75_P75") (pintype "bidirectional"))
      (node (ref "R126") (pin "2") (pinfunction "2_2") (pintype "passive"))
      (node (ref "R127") (pin "2") (pinfunction "2_2") (pintype "passive"))
      (node (ref "R128") (pin "2") (pinfunction "2_2") (pintype "passive"))
      (node (ref "R129") (pin "2") (pinfunction "2_2") (pintype "passive"))
      (node (ref "R130") (pin "2") (pinfunction "2_2") (pintype "passive"))
      (node (ref "R131") (pin "2") (pinfunction "2_2") (pintype "passive"))
      (node (ref "R132") (pin "2") (pinfunction "2_2") (pintype "passive"))
      (node (ref "R133") (pin "2") (pinfunction "2_2") (pintype "passive"))
      (node (ref "R139") (pin "2") (pinfunction "2_2") (pintype "passive"))
      (node (ref "R140") (pin "1") (pinfunction "1_1") (pintype "passive"))
      (node (ref "R142") (pin "2") (pinfunction "2_2") (pintype "passive"))
      (node (ref "X5") (pin "2") (pinfunction "Y_2") (pintype "passive"))
    )
    (net (code "67") (name "Net-(C167-Pad1)") (class "Default")
      (node (ref "C167") (pin "1") (pinfunction "1_1") (pintype "passive"))
      (node (ref "L1") (pin "2") (pinfunction "2_2") (pintype "passive"))
      (node (ref "R113") (pin "1") (pinfunction "1_1") (pintype "passive"))
    )
    (net (code "68") (name "Net-(C170-Pad1)") (class "Default")
      (node (ref "C170") (pin "1") (pinfunction "1_1") (pintype "passive"))
      (node (ref "FR37") (pin "1") (pinfunction "1_1") (pintype "passive"))
      (node (ref "R114") (pin "2") (pinfunction "2_2") (pintype "passive"))
    )
    (net (code "69") (name "Net-(IC11-UART_RX)") (class "Default")
      (node (ref "FR36") (pin "2") (pinfunction "2_2") (pintype "passive"))
      (node (ref "IC11") (pin "9") (pinfunction "UART_RX_9") (pintype "input"))
    )
    (net (code "70") (name "Net-(IC11-UART_TX)") (class "Default")
      (node (ref "FR37") (pin "2") (pinfunction "2_2") (pintype "passive"))
      (node (ref "IC11") (pin "10") (pinfunction "UART_TX_10") (pintype "output"))
    )
    (net (code "71") (name "Net-(LED1-C)") (class "Default")
      (node (ref "LED1") (pin "K") (pinfunction "C_K") (pintype "power_in"))
      (node (ref "R141") (pin "1") (pinfunction "1_1") (pintype "passive"))
    )
    (net (code "72") (name "Net-(LED2-C)") (class "Default")
      (node (ref "LED2") (pin "K") (pinfunction "C_K") (pintype "power_in"))
      (node (ref "R147") (pin "1") (pinfunction "1_1") (pintype "passive"))
    )
    (net (code "73") (name "VCC1P8") (class "Default")
      (node (ref "C163") (pin "2") (pinfunction "2_2") (pintype "passive"))
      (node (ref "C165") (pin "2") (pinfunction "2_2") (pintype "passive"))
      (node (ref "C172") (pin "2") (pinfunction "2_2") (pintype "passive"))
      (node (ref "IC12") (pin "14") (pinfunction "VCCA_14") (pintype "passive"))
      (node (ref "IC12") (pin "15") (pinfunction "DIR1_15") (pintype "passive"))
      (node (ref "IC12") (pin "16") (pinfunction "DIR2_16") (pintype "passive"))
      (node (ref "IC12") (pin "6") (pinfunction "DIR4_6") (pintype "passive"))
      (node (ref "IC8") (pin "14") (pinfunction "VCCA_14") (pintype "passive"))
      (node (ref "IC8") (pin "15") (pinfunction "DIR1_15") (pintype "passive"))
      (node (ref "IC8") (pin "5") (pinfunction "DIR3_5") (pintype "passive"))
      (node (ref "IC9") (pin "14") (pinfunction "VCCA_14") (pintype "passive"))
      (node (ref "IC9") (pin "15") (pinfunction "DIR1_15") (pintype "passive"))
      (node (ref "IC9") (pin "16") (pinfunction "DIR2_16") (pintype "passive"))
      (node (ref "IC9") (pin "5") (pinfunction "DIR3_5") (pintype "passive"))
      (node (ref "IC9") (pin "6") (pinfunction "DIR4_6") (pintype "passive"))
      (node (ref "R115") (pin "1") (pinfunction "1_1") (pintype "passive"))
      (node (ref "R116") (pin "1") (pinfunction "1_1") (pintype "passive"))
      (node (ref "R117") (pin "1") (pinfunction "1_1") (pintype "passive"))
      (node (ref "R118") (pin "1") (pinfunction "1_1") (pintype "passive"))
      (node (ref "R119") (pin "1") (pinfunction "1_1") (pintype "passive"))
      (node (ref "R120") (pin "1") (pinfunction "1_1") (pintype "passive"))
      (node (ref "R121") (pin "1") (pinfunction "1_1") (pintype "passive"))
      (node (ref "R122") (pin "1") (pinfunction "1_1") (pintype "passive"))
      (node (ref "R123") (pin "1") (pinfunction "1_1") (pintype "passive"))
      (node (ref "R124") (pin "1") (pinfunction "1_1") (pintype "passive"))
      (node (ref "R144") (pin "1") (pinfunction "1_1") (pintype "passive"))
      (node (ref "R145") (pin "1") (pinfunction "1_1") (pintype "passive"))
      (node (ref "R148") (pin "1") (pinfunction "1_1") (pintype "passive"))
      (node (ref "VT1") (pin "G") (pinfunction "G_G") (pintype "passive"))
      (node (ref "VT2") (pin "G") (pinfunction "G_G") (pintype "passive"))
    )
    (net (code "74") (name "VCC3P3") (class "Default")
      (node (ref "C164") (pin "1") (pinfunction "1_1") (pintype "passive"))
      (node (ref "C166") (pin "1") (pinfunction "1_1") (pintype "passive"))
      (node (ref "C168") (pin "1") (pinfunction "1_1") (pintype "passive"))
      (node (ref "C173") (pin "1") (pinfunction "1_1") (pintype "passive"))
      (node (ref "C177") (pin "1") (pinfunction "1_1") (pintype "passive"))
      (node (ref "C179") (pin "1") (pinfunction "1_1") (pintype "passive"))
      (node (ref "IC10") (pin "5") (pinfunction "V+_5") (pintype "power_in"))
      (node (ref "IC12") (pin "13") (pinfunction "VCCB_13") (pintype "passive"))
      (node (ref "IC13") (pin "8") (pinfunction "VCC_8") (pintype "power_in"))
      (node (ref "IC14") (pin "5") (pinfunction "VDD_5") (pintype "power_in"))
      (node (ref "IC8") (pin "13") (pinfunction "VCCB_13") (pintype "passive"))
      (node (ref "IC9") (pin "13") (pinfunction "VCCB_13") (pintype "passive"))
      (node (ref "J2") (pin "7") (pinfunction "7_7") (pintype "passive"))
      (node (ref "LED1") (pin "A") (pinfunction "A_A") (pintype "power_in"))
      (node (ref "LED2") (pin "A") (pinfunction "A_A") (pintype "power_in"))
      (node (ref "R135") (pin "1") (pinfunction "1_1") (pintype "passive"))
      (node (ref "R143") (pin "1") (pinfunction "1_1") (pintype "passive"))
      (node (ref "R149") (pin "1") (pinfunction "1_1") (pintype "passive"))
      (node (ref "R150") (pin "1") (pinfunction "1_1") (pintype "passive"))
    )
    (net (code "75") (name "VCC3P3_CLK") (class "Default")
      (node (ref "FR38") (pin "1") (pinfunction "1_1") (pintype "passive"))
    )
    (net (code "76") (name "VCC3P3_GNSS") (class "Default")
      (node (ref "C175") (pin "2") (pinfunction "2_2") (pintype "passive"))
      (node (ref "C176") (pin "2") (pinfunction "2_2") (pintype "passive"))
      (node (ref "FR38") (pin "2") (pinfunction "2_2") (pintype "passive"))
      (node (ref "IC11") (pin "14") (pinfunction "BV_14") (pintype "power_in"))
      (node (ref "IC11") (pin "15") (pinfunction "VCC_15") (pintype "power_in"))
      (node (ref "R113") (pin "2") (pinfunction "2_2") (pintype "passive"))
    )
    (net (code "77") (name "VCC3P3_M.2") (class "Default")
      (node (ref "J3") (pin "P2") (pinfunction "2_P2") (pintype "bidirectional"))
      (node (ref "J3") (pin "P4") (pinfunction "4_P4") (pintype "bidirectional"))
      (node (ref "J3") (pin "P70") (pinfunction "70_P70") (pintype "bidirectional"))
      (node (ref "J3") (pin "P72") (pinfunction "72_P72") (pintype "bidirectional"))
      (node (ref "J3") (pin "P74") (pinfunction "74_P74") (pintype "bidirectional"))
    )
    (net (code "78") (name "VCC_EXT") (class "Default")
      (node (ref "J2") (pin "8") (pinfunction "8_8") (pintype "passive"))
    )
    (net (code "79") (name "unconnected-(IC8-A4-Pad4)") (class "Default")
      (node (ref "IC8") (pin "4") (pinfunction "A4_4") (pintype "passive+no_connect"))
    )
    (net (code "80") (name "unconnected-(IC9-B1-Pad12)") (class "Default")
      (node (ref "IC9") (pin "12") (pinfunction "B1_12") (pintype "passive+no_connect"))
    )
    (net (code "81") (name "unconnected-(IC9-B2-Pad11)") (class "Default")
      (node (ref "IC9") (pin "11") (pinfunction "B2_11") (pintype "passive+no_connect"))
    )
    (net (code "82") (name "unconnected-(IC10-ALERT-Pad3)") (class "Default")
      (node (ref "IC10") (pin "3") (pinfunction "ALERT_3") (pintype "output+no_connect"))
    )
    (net (code "83") (name "unconnected-(IC11-E2-Pad11)") (class "Default")
      (node (ref "IC11") (pin "11") (pinfunction "E2_11") (pintype "passive+no_connect"))
    )
    (net (code "84") (name "unconnected-(IC11-E3-Pad12)") (class "Default")
      (node (ref "IC11") (pin "12") (pinfunction "E3_12") (pintype "passive+no_connect"))
    )
    (net (code "85") (name "unconnected-(IC14-INTA-Pad16)") (class "Default")
      (node (ref "IC14") (pin "16") (pinfunction "INTA_16") (pintype "open_collector+no_connect"))
    )
    (net (code "86") (name "unconnected-(IC14-INTB-Pad15)") (class "Default")
      (node (ref "IC14") (pin "15") (pinfunction "INTB_15") (pintype "open_collector+no_connect"))
    )
    (net (code "87") (name "unconnected-(IC14-NC-Pad7)") (class "Default")
      (node (ref "IC14") (pin "7") (pinfunction "NC_7") (pintype "passive+no_connect"))
    )
    (net (code "88") (name "unconnected-(IC14-NC-Pad10)") (class "Default")
      (node (ref "IC14") (pin "10") (pinfunction "NC_10") (pintype "passive+no_connect"))
    )
    (net (code "89") (name "unconnected-(J3A-5-PadP5)") (class "Default")
      (node (ref "J3") (pin "P5") (pinfunction "5_P5") (pintype "bidirectional+no_connect"))
    )
    (net (code "90") (name "unconnected-(J3A-7-PadP7)") (class "Default")
      (node (ref "J3") (pin "P7") (pinfunction "7_P7") (pintype "bidirectional+no_connect"))
    )
    (net (code "91") (name "unconnected-(J3A-9-PadP9)") (class "Default")
      (node (ref "J3") (pin "P9") (pinfunction "9_P9") (pintype "bidirectional+no_connect"))
    )
    (net (code "92") (name "unconnected-(J3A-11-PadP11)") (class "Default")
      (node (ref "J3") (pin "P11") (pinfunction "11_P11") (pintype "bidirectional+no_connect"))
    )
    (net (code "93") (name "unconnected-(J3A-23-PadP23)") (class "Default")
      (node (ref "J3") (pin "P23") (pinfunction "23_P23") (pintype "bidirectional+no_connect"))
    )
    (net (code "94") (name "unconnected-(J3A-25-PadP25)") (class "Default")
      (node (ref "J3") (pin "P25") (pinfunction "25_P25") (pintype "bidirectional+no_connect"))
    )
    (net (code "95") (name "unconnected-(J3A-29-PadP29)") (class "Default")
      (node (ref "J3") (pin "P29") (pinfunction "29_P29") (pintype "bidirectional+no_connect"))
    )
    (net (code "96") (name "unconnected-(J3A-31-PadP31)") (class "Default")
      (node (ref "J3") (pin "P31") (pinfunction "31_P31") (pintype "bidirectional+no_connect"))
    )
    (net (code "97") (name "unconnected-(J3A-35-PadP35)") (class "Default")
      (node (ref "J3") (pin "P35") (pinfunction "35_P35") (pintype "bidirectional+no_connect"))
    )
    (net (code "98") (name "unconnected-(J3A-37-PadP37)") (class "Default")
      (node (ref "J3") (pin "P37") (pinfunction "37_P37") (pintype "bidirectional+no_connect"))
    )
    (net (code "99") (name "unconnected-(J3A-67-PadP67)") (class "Default")
      (node (ref "J3") (pin "P67") (pinfunction "67_P67") (pintype "bidirectional+no_connect"))
    )
    (net (code "100") (name "unconnected-(J3A-69-PadP69)") (class "Default")
      (node (ref "J3") (pin "P69") (pinfunction "69_P69") (pintype "bidirectional+no_connect"))
    )
    (net (code "101") (name "unconnected-(J3B-6-PadP6)") (class "Default")
      (node (ref "J3") (pin "P6") (pinfunction "6_P6") (pintype "bidirectional+no_connect"))
    )
    (net (code "102") (name "unconnected-(J3B-30-PadP30)") (class "Default")
      (node (ref "J3") (pin "P30") (pinfunction "30_P30") (pintype "bidirectional+no_connect"))
    )
    (net (code "103") (name "unconnected-(J3B-32-PadP32)") (class "Default")
      (node (ref "J3") (pin "P32") (pinfunction "32_P32") (pintype "bidirectional+no_connect"))
    )
    (net (code "104") (name "unconnected-(J3B-34-PadP34)") (class "Default")
      (node (ref "J3") (pin "P34") (pinfunction "34_P34") (pintype "bidirectional+no_connect"))
    )
    (net (code "105") (name "unconnected-(J3B-36-PadP36)") (class "Default")
      (node (ref "J3") (pin "P36") (pinfunction "36_P36") (pintype "bidirectional+no_connect"))
    )
    (net (code "106") (name "unconnected-(J3B-38-PadP38)") (class "Default")
      (node (ref "J3") (pin "P38") (pinfunction "38_P38") (pintype "bidirectional+no_connect"))
    )
    (net (code "107") (name "unconnected-(J3B-40-PadP40)") (class "Default")
      (node (ref "J3") (pin "P40") (pinfunction "40_P40") (pintype "bidirectional+no_connect"))
    )
    (net (code "108") (name "unconnected-(J3B-42-PadP42)") (class "Default")
      (node (ref "J3") (pin "P42") (pinfunction "42_P42") (pintype "bidirectional+no_connect"))
    )
    (net (code "109") (name "unconnected-(J3B-44-PadP44)") (class "Default")
      (node (ref "J3") (pin "P44") (pinfunction "44_P44") (pintype "bidirectional+no_connect"))
    )
    (net (code "110") (name "unconnected-(J3B-54-PadP54)") (class "Default")
      (node (ref "J3") (pin "P54") (pinfunction "54_P54") (pintype "bidirectional+no_connect"))
    )
    (net (code "111") (name "unconnected-(J3B-56-PadP56)") (class "Default")
      (node (ref "J3") (pin "P56") (pinfunction "56_P56") (pintype "bidirectional+no_connect"))
    )
    (net (code "112") (name "unconnected-(J3B-58-PadP58)") (class "Default")
      (node (ref "J3") (pin "P58") (pinfunction "58_P58") (pintype "bidirectional+no_connect"))
    )
    (net (code "113") (name "unconnected-(J3B-68-PadP68)") (class "Default")
      (node (ref "J3") (pin "P68") (pinfunction "68_P68") (pintype "bidirectional+no_connect"))
    )
  )
)
